# SD_CARD.net
KiCad netlist of a schematic drawn in Altium Designer
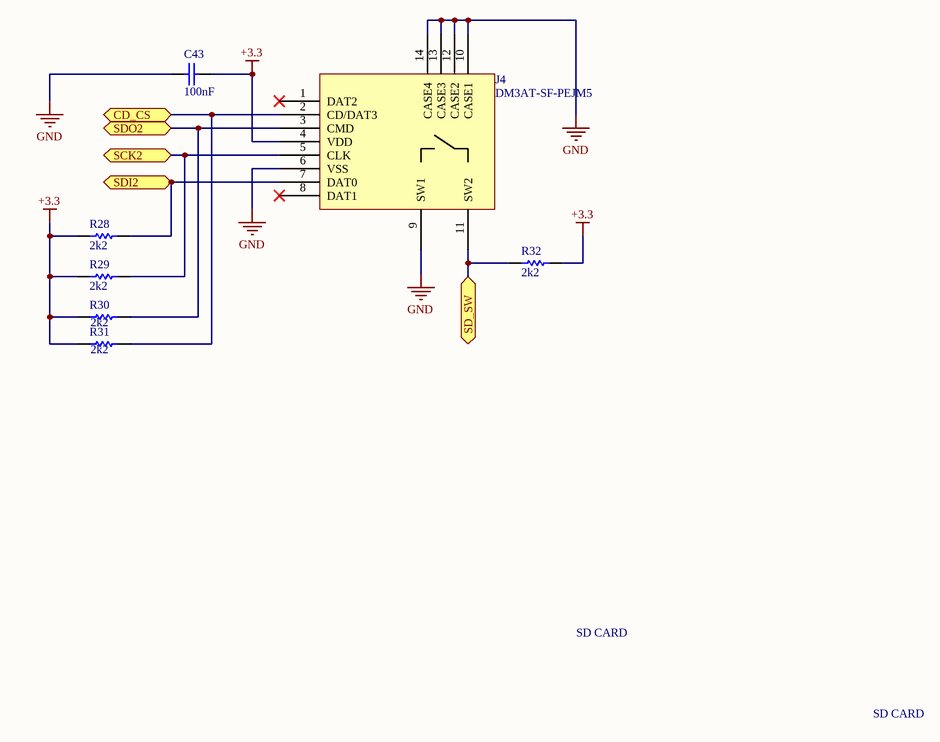
[diagram p0: SD CARD.SchDoc]

(export (version "E")
  (design (tool "Eeschema 10.0.6"))
  (components
    (comp (ref "C43")
      (value "100nF")
      (footprint "WCAP-CSGP_0603, 1.6x0.8x0.8mm_Reflow")
      (description "WCAP-CSGP Ceramic Capacitors, size 0603, 1.6x0.8x0.8mm, 10V, X7R, 100nF")
      (fields (field (name "PART NUMBER") "885012206020") (field (name "PUBLISHER") "Wurth Elektronik"))
      (libsource (lib "Altium_WCAP-CSGP (rev17a)") (part "885012206020"))
    )
    (comp (ref "J4")
      (value "DM3AT-SF-PEJM5")
      (footprint "SD CARD MICRO")
      (description "Conector micro SD push/push")
      (libsource (lib "Componentes Deived Projetos") (part "DM3AT-SF-PEJM5"))
    )
    (comp (ref "R28")
      (value "2k2")
      (footprint "3-0603")
      (fields (field (name "PUBLISHER") "Altium Limited"))
      (libsource (lib "Panasonic Resistor") (part "ERJ3RE"))
    )
    (comp (ref "R29")
      (value "2k2")
      (footprint "3-0603")
      (fields (field (name "PUBLISHER") "Altium Limited"))
      (libsource (lib "Panasonic Resistor") (part "ERJ3RE"))
    )
    (comp (ref "R30")
      (value "2k2")
      (footprint "3-0603")
      (fields (field (name "PUBLISHER") "Altium Limited"))
      (libsource (lib "Panasonic Resistor") (part "ERJ3RE"))
    )
    (comp (ref "R31")
      (value "2k2")
      (footprint "3-0603")
      (fields (field (name "PUBLISHER") "Altium Limited"))
      (libsource (lib "Panasonic Resistor") (part "ERJ3RE"))
    )
    (comp (ref "R32")
      (value "2k2")
      (footprint "3-0603")
      (fields (field (name "PUBLISHER") "Altium Limited"))
      (libsource (lib "Panasonic Resistor") (part "ERJ3RE"))
    )
  )
  (nets
    (net (code "1") (name "+3.3") (class "Default")
      (node (ref "C43") (pin "2") (pinfunction "2_2") (pintype "passive"))
      (node (ref "J4") (pin "4") (pinfunction "VDD_4") (pintype "passive"))
      (node (ref "R28") (pin "1") (pinfunction "1_1") (pintype "passive"))
      (node (ref "R29") (pin "1") (pinfunction "1_1") (pintype "passive"))
      (node (ref "R30") (pin "1") (pinfunction "1_1") (pintype "passive"))
      (node (ref "R31") (pin "1") (pinfunction "1_1") (pintype "passive"))
      (node (ref "R32") (pin "2") (pinfunction "2_2") (pintype "passive"))
    )
    (net (code "2") (name "/CD_CS") (class "Default")
      (node (ref "J4") (pin "2") (pinfunction "CD/DAT3_2") (pintype "passive"))
      (node (ref "R31") (pin "2") (pinfunction "2_2") (pintype "passive"))
    )
    (net (code "3") (name "/SCK2") (class "Default")
      (node (ref "J4") (pin "5") (pinfunction "CLK_5") (pintype "passive"))
      (node (ref "R29") (pin "2") (pinfunction "2_2") (pintype "passive"))
    )
    (net (code "4") (name "/SDI2") (class "Default")
      (node (ref "J4") (pin "7") (pinfunction "DAT0_7") (pintype "passive"))
      (node (ref "R28") (pin "2") (pinfunction "2_2") (pintype "passive"))
    )
    (net (code "5") (name "/SDO2") (class "Default")
      (node (ref "J4") (pin "3") (pinfunction "CMD_3") (pintype "passive"))
      (node (ref "R30") (pin "2") (pinfunction "2_2") (pintype "passive"))
    )
    (net (code "6") (name "/SD_SW") (class "Default")
      (node (ref "J4") (pin "11") (pinfunction "SW2_11") (pintype "passive"))
      (node (ref "R32") (pin "1") (pinfunction "1_1") (pintype "passive"))
    )
    (net (code "7") (name "GND") (class "Default")
      (node (ref "C43") (pin "1") (pinfunction "1_1") (pintype "passive"))
      (node (ref "J4") (pin "10") (pinfunction "CASE1_10") (pintype "passive"))
      (node (ref "J4") (pin "12") (pinfunction "CASE2_12") (pintype "passive"))
      (node (ref "J4") (pin "13") (pinfunction "CASE3_13") (pintype "passive"))
      (node (ref "J4") (pin "14") (pinfunction "CASE4_14") (pintype "passive"))
      (node (ref "J4") (pin "6") (pinfunction "VSS_6") (pintype "passive"))
      (node (ref "J4") (pin "9") (pinfunction "SW1_9") (pintype "passive"))
    )
    (net (code "8") (name "unconnected-(J4-DAT1-Pad8)") (class "Default")
      (node (ref "J4") (pin "8") (pinfunction "DAT1_8") (pintype "passive+no_connect"))
    )
    (net (code "9") (name "unconnected-(J4-DAT2-Pad1)") (class "Default")
      (node (ref "J4") (pin "1") (pinfunction "DAT2_1") (pintype "passive+no_connect"))
    )
  )
)
